# LED_Button.net
KiCad netlist of a schematic drawn in Altium Designer
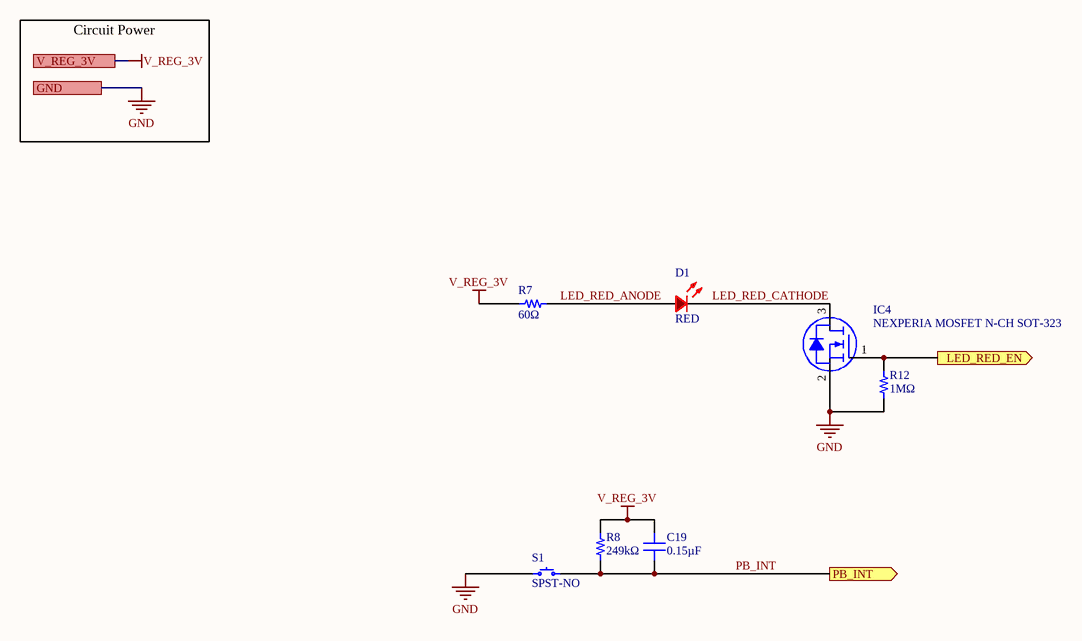
[diagram p0: LED & Button.SchDoc]

(export (version "E")
  (design (tool "Eeschema 10.0.6"))
  (components
    (comp (ref "C19")
      (value "0.15µF")
      (footprint "CAP 0603_1608")
      (description "CAP CER 0.15UF 10V X7R 0603")
      (fields (field (name "MANUFACTURER") "KEMET") (field (name "VOLTAGE") "10V"))
      (libsource (lib "MVVVMAltiumDatabase") (part "Capacitor"))
    )
    (comp (ref "D1")
      (value "RED")
      (footprint "LED 0603_1608")
      (description "LED RED CLEAR 0603 SMD")
      (fields (field (name "MANUFACTURER") "Würth Elektronik"))
      (libsource (lib "MVVVMAltiumDatabase") (part "LED_RED"))
    )
    (comp (ref "IC4")
      (value "NEXPERIA MOSFET N-CH SOT-323")
      (footprint "NEXPERIA SOT-323")
      (description "MOSFET N-CH 60V 320MA SOT323")
      (fields (field (name "MANUFACTURER") "Nexperia USA Inc."))
      (libsource (lib "MVVVMAltiumDatabase") (part "NEXPERIA MOSFET N-CH SOT-323"))
    )
    (comp (ref "R7")
      (value "60Ω")
      (footprint "RES 0603_1608 RF")
      (description "RES 60 OHM 1% 1/10W 0603")
      (fields (field (name "MANUFACTURER") "Vishay Dale") (field (name "TOLERANCE") "±1%"))
      (libsource (lib "MVVVMAltiumDatabase") (part "Resistor"))
    )
    (comp (ref "R8")
      (value "249kΩ")
      (footprint "RES 0603_1608 RF")
      (description "RES SMD 249K OHM 0.1% 1/10W 0603")
      (fields (field (name "MANUFACTURER") "Susumu") (field (name "TOLERANCE") "±0.1%"))
      (libsource (lib "MVVVMAltiumDatabase") (part "Resistor"))
    )
    (comp (ref "R12")
      (value "1MΩ")
      (footprint "RES 0603_1608 RF")
      (description "RES 1M OHM 1% 1/10W 0603")
      (fields (field (name "MANUFACTURER") "Vishay Dale") (field (name "TOLERANCE") "±1%"))
      (libsource (lib "MVVVMAltiumDatabase") (part "Resistor"))
    )
    (comp (ref "S1")
      (value "SPST-NO")
      (footprint "PANASONIC EVP-AA002K")
      (description "SWITCH TACTILE SPST-NO 0.02A 15V")
      (fields (field (name "MANUFACTURER") "Panasonic Electronic Components"))
      (libsource (lib "MVVVMAltiumDatabase") (part "SPST-NO 2 PIN"))
    )
  )
  (nets
    (net (code "1") (name "/LED_RED_ANODE") (class "Default")
      (node (ref "D1") (pin "1") (pinfunction "1_1") (pintype "passive"))
      (node (ref "R7") (pin "2") (pinfunction "2_2") (pintype "passive"))
    )
    (net (code "2") (name "/LED_RED_CATHODE") (class "Default")
      (node (ref "D1") (pin "2") (pinfunction "2_2") (pintype "passive"))
      (node (ref "IC4") (pin "3") (pinfunction "D_3") (pintype "passive"))
    )
    (net (code "3") (name "/LED_RED_EN") (class "Default")
      (node (ref "IC4") (pin "1") (pinfunction "G_1") (pintype "passive"))
      (node (ref "R12") (pin "2") (pinfunction "2_2") (pintype "passive"))
    )
    (net (code "4") (name "/PB_INT") (class "Default")
      (node (ref "C19") (pin "1") (pinfunction "1_1") (pintype "passive"))
      (node (ref "R8") (pin "1") (pinfunction "1_1") (pintype "passive"))
      (node (ref "S1") (pin "2") (pinfunction "2_2") (pintype "passive"))
    )
    (net (code "5") (name "GND") (class "Default")
      (node (ref "IC4") (pin "2") (pinfunction "S_2") (pintype "passive"))
      (node (ref "R12") (pin "1") (pinfunction "1_1") (pintype "passive"))
      (node (ref "S1") (pin "1") (pinfunction "1_1") (pintype "passive"))
    )
    (net (code "6") (name "V_REG_3V") (class "Default")
      (node (ref "C19") (pin "2") (pinfunction "2_2") (pintype "passive"))
      (node (ref "R7") (pin "1") (pinfunction "1_1") (pintype "passive"))
      (node (ref "R8") (pin "2") (pinfunction "2_2") (pintype "passive"))
    )
  )
)
